# CV_Recorder.net
KiCad netlist of a schematic drawn in EAGLE
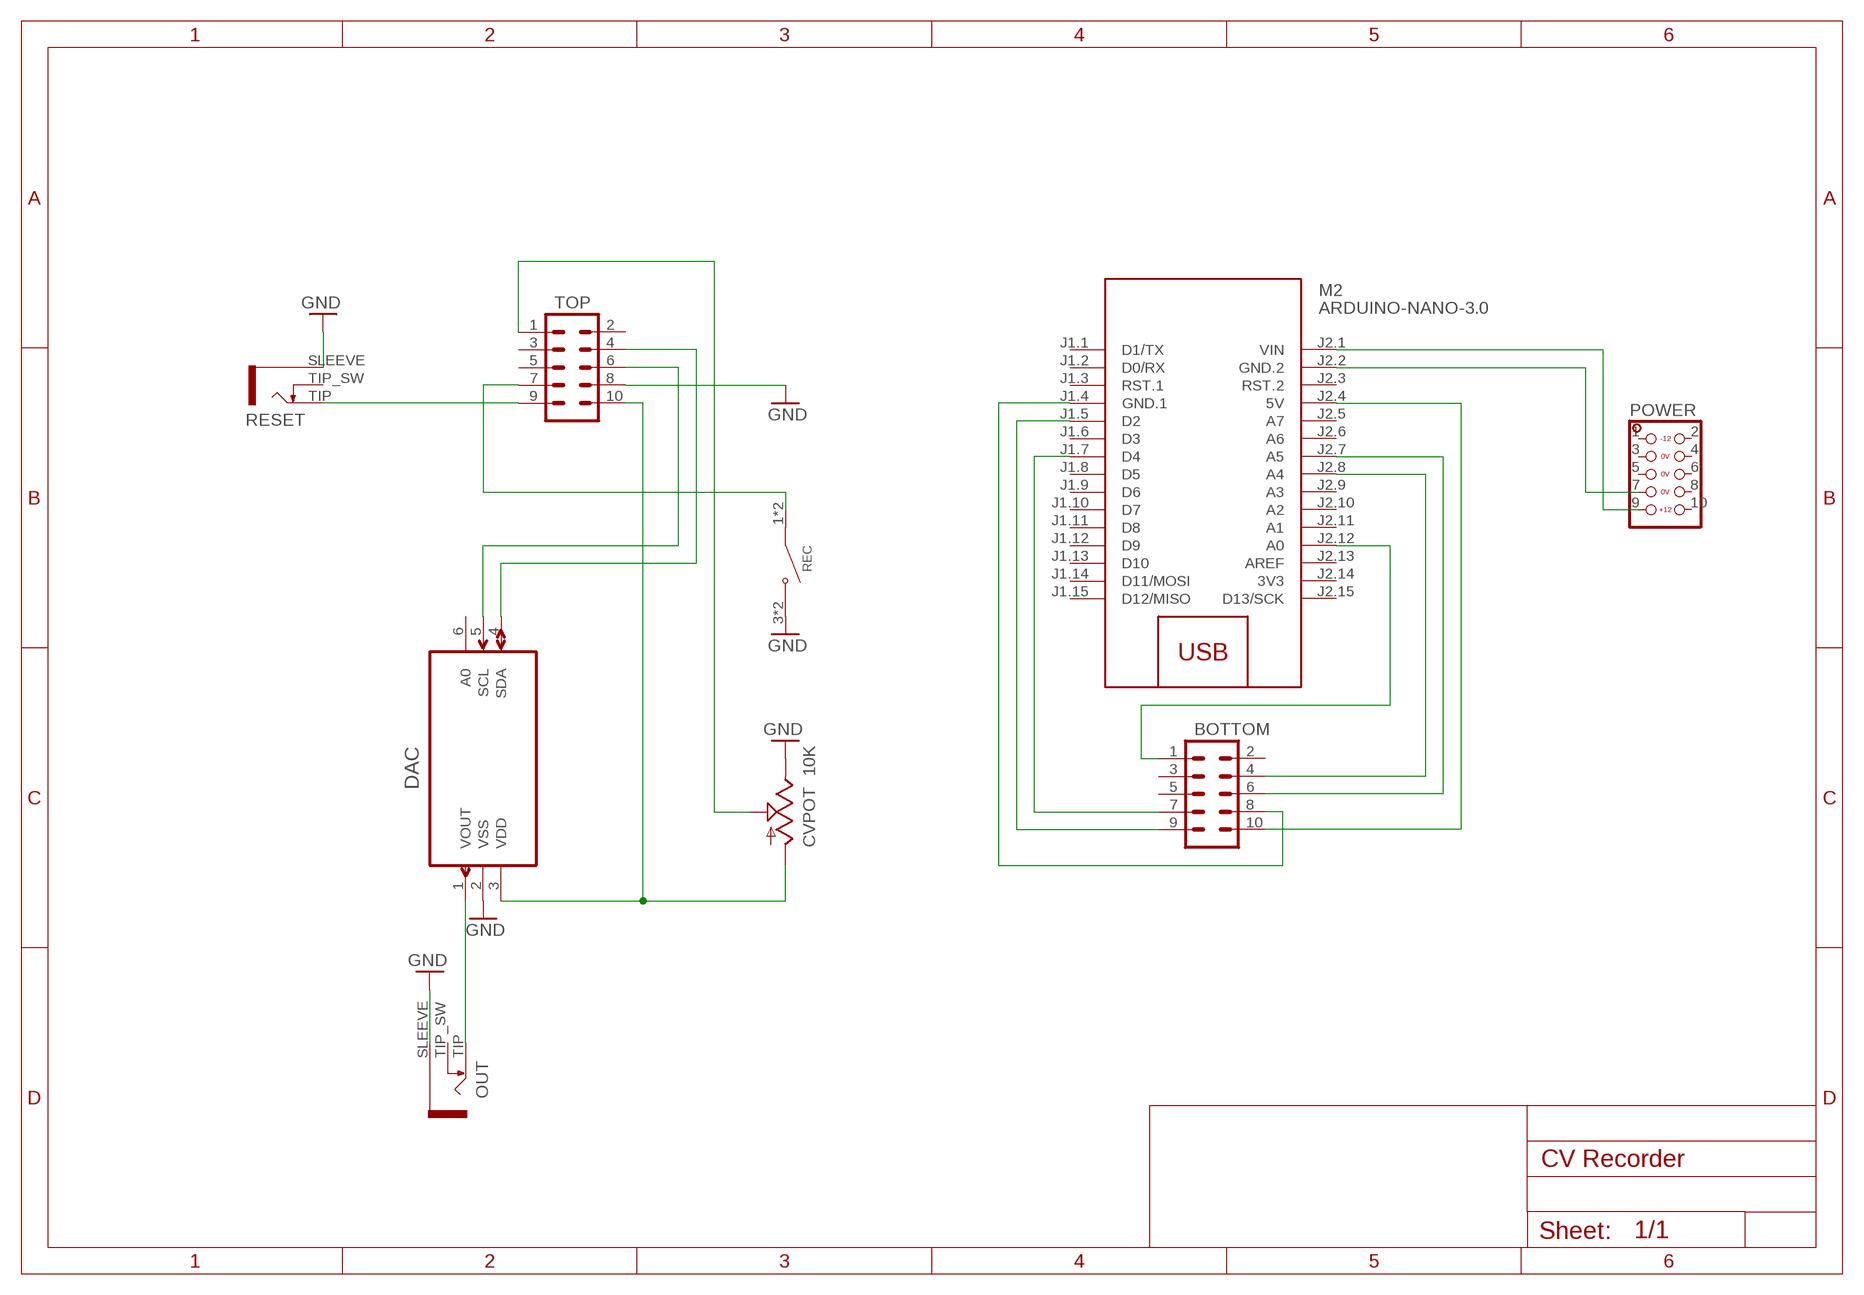
[diagram p0: schematic, sheet 1]

(export (version "E")
  (design (tool "Eeschema 10.0.6"))
  (components
    (comp (ref "BOTTOM")
      (value "M05X2PTH")
      (footprint "eagle-import:2X5")
      (libsource (lib "eagle-import") (part "M05X2PTH"))
    )
    (comp (ref "CVPOT")
      (value "10K")
      (footprint "eagle-import:ALPS_POT")
      (libsource (lib "eagle-import") (part "POT"))
    )
    (comp (ref "DAC")
      (value "MCP4725A0T-E/CH")
      (footprint "eagle-import:SOT95P270X145-6N")
      (libsource (lib "eagle-import") (part "MCP4725A0T-E/CH"))
    )
    (comp (ref "M2")
      (value "ARDUINO-NANO-3.0")
      (footprint "eagle-import:ARDUINO-NANO-3.0")
      (libsource (lib "eagle-import") (part "ARDUINO-NANO-3.0"))
    )
    (comp (ref "OUT")
      (value "JACK-3_5MM-MONO-SW-ALT")
      (footprint "eagle-import:WQP_PJ301M_ALT")
      (libsource (lib "eagle-import") (part "JACK-3_5MM-MONO-SW-ALT"))
    )
    (comp (ref "POWER")
      (value "EUROPWR_2X05-OPEN")
      (footprint "eagle-import:2X05_EUROPWR_OPEN")
      (libsource (lib "eagle-import") (part "EUROPWR_2X05-OPEN"))
    )
    (comp (ref "REC")
      (value "D6R90_F1_LFS")
      (footprint "eagle-import:SW_D6R90_F1_LFS")
      (fields (field (name "MF") "C&K") (field (name "MP") "D6R90 F1 LFS"))
      (libsource (lib "eagle-import") (part "D6R90_F1_LFS"))
    )
    (comp (ref "RESET")
      (value "JACK-3_5MM-MONO-SW-ALT")
      (footprint "eagle-import:WQP_PJ301M_ALT")
      (libsource (lib "eagle-import") (part "JACK-3_5MM-MONO-SW-ALT"))
    )
    (comp (ref "TOP")
      (value "M05X2PTH")
      (footprint "eagle-import:2X5")
      (libsource (lib "eagle-import") (part "M05X2PTH"))
    )
  )
  (nets
    (net (code "1") (name "/3V3") (class "Default")
      (node (ref "M2") (pin "J2.14") (pinfunction "3V3_J2.14") (pintype "power_in"))
    )
    (net (code "2") (name "GND") (class "Default")
      (node (ref "CVPOT") (pin "P$1") (pinfunction "3_P$1") (pintype "passive"))
      (node (ref "DAC") (pin "2") (pinfunction "VSS_2") (pintype "power_in"))
      (node (ref "OUT") (pin "SLEEVE") (pinfunction "SLEEVE_SLEEVE") (pintype "passive"))
      (node (ref "REC") (pin "3") (pinfunction "NO_3") (pintype "passive"))
      (node (ref "REC") (pin "4") (pinfunction "NO_4") (pintype "passive"))
      (node (ref "RESET") (pin "SLEEVE") (pinfunction "SLEEVE_SLEEVE") (pintype "passive"))
      (node (ref "TOP") (pin "8") (pinfunction "8_8") (pintype "passive"))
    )
    (net (code "3") (name "Net-(CVPOT-1)") (class "Default")
      (node (ref "CVPOT") (pin "P$3") (pinfunction "1_P$3") (pintype "passive"))
      (node (ref "DAC") (pin "3") (pinfunction "VDD_3") (pintype "power_in"))
      (node (ref "TOP") (pin "10") (pinfunction "10_10") (pintype "passive"))
    )
    (net (code "4") (name "Net-(CVPOT-2)") (class "Default")
      (node (ref "CVPOT") (pin "P$2") (pinfunction "2_P$2") (pintype "passive"))
      (node (ref "TOP") (pin "1") (pinfunction "1_1") (pintype "passive"))
    )
    (net (code "5") (name "Net-(DAC-SCL)") (class "Default")
      (node (ref "DAC") (pin "5") (pinfunction "SCL_5") (pintype "input"))
      (node (ref "TOP") (pin "6") (pinfunction "6_6") (pintype "passive"))
    )
    (net (code "6") (name "Net-(DAC-SDA)") (class "Default")
      (node (ref "DAC") (pin "4") (pinfunction "SDA_4") (pintype "bidirectional"))
      (node (ref "TOP") (pin "4") (pinfunction "4_4") (pintype "passive"))
    )
    (net (code "7") (name "Net-(DAC-VOUT)") (class "Default")
      (node (ref "DAC") (pin "1") (pinfunction "VOUT_1") (pintype "output"))
      (node (ref "OUT") (pin "TIP") (pinfunction "TIP_TIP") (pintype "passive"))
    )
    (net (code "8") (name "Net-(M2-5V)") (class "Default")
      (node (ref "BOTTOM") (pin "10") (pinfunction "10_10") (pintype "passive"))
      (node (ref "M2") (pin "J2.4") (pinfunction "5V_J2.4") (pintype "power_in"))
    )
    (net (code "9") (name "Net-(M2-A0)") (class "Default")
      (node (ref "BOTTOM") (pin "1") (pinfunction "1_1") (pintype "passive"))
      (node (ref "M2") (pin "J2.12") (pinfunction "A0_J2.12") (pintype "bidirectional"))
    )
    (net (code "10") (name "Net-(M2-A4)") (class "Default")
      (node (ref "BOTTOM") (pin "4") (pinfunction "4_4") (pintype "passive"))
      (node (ref "M2") (pin "J2.8") (pinfunction "A4_J2.8") (pintype "bidirectional"))
    )
    (net (code "11") (name "Net-(M2-A5)") (class "Default")
      (node (ref "BOTTOM") (pin "6") (pinfunction "6_6") (pintype "passive"))
      (node (ref "M2") (pin "J2.7") (pinfunction "A5_J2.7") (pintype "bidirectional"))
    )
    (net (code "12") (name "Net-(M2-D2)") (class "Default")
      (node (ref "BOTTOM") (pin "9") (pinfunction "9_9") (pintype "passive"))
      (node (ref "M2") (pin "J1.5") (pinfunction "D2_J1.5") (pintype "bidirectional"))
    )
    (net (code "13") (name "Net-(M2-D4)") (class "Default")
      (node (ref "BOTTOM") (pin "7") (pinfunction "7_7") (pintype "passive"))
      (node (ref "M2") (pin "J1.7") (pinfunction "D4_J1.7") (pintype "bidirectional"))
    )
    (net (code "14") (name "Net-(M2-GND.1)") (class "Default")
      (node (ref "BOTTOM") (pin "8") (pinfunction "8_8") (pintype "passive"))
      (node (ref "M2") (pin "J1.4") (pinfunction "GND.1_J1.4") (pintype "power_in"))
    )
    (net (code "15") (name "Net-(M2-GND.2)") (class "Default")
      (node (ref "M2") (pin "J2.2") (pinfunction "GND.2_J2.2") (pintype "power_in"))
      (node (ref "POWER") (pin "7") (pinfunction "7_7") (pintype "passive"))
    )
    (net (code "16") (name "Net-(M2-VIN)") (class "Default")
      (node (ref "M2") (pin "J2.1") (pinfunction "VIN_J2.1") (pintype "power_in"))
      (node (ref "POWER") (pin "9") (pinfunction "9_9") (pintype "passive"))
    )
    (net (code "17") (name "Net-(REC-COM-Pad1)") (class "Default")
      (node (ref "REC") (pin "1") (pinfunction "COM_1") (pintype "passive"))
      (node (ref "REC") (pin "2") (pinfunction "COM_2") (pintype "passive"))
      (node (ref "TOP") (pin "7") (pinfunction "7_7") (pintype "passive"))
    )
    (net (code "18") (name "Net-(RESET-PadTIP)") (class "Default")
      (node (ref "RESET") (pin "TIP") (pinfunction "TIP_TIP") (pintype "passive"))
      (node (ref "TOP") (pin "9") (pinfunction "9_9") (pintype "passive"))
    )
    (net (code "19") (name "unconnected-(BOTTOM-Pad2)") (class "Default")
      (node (ref "BOTTOM") (pin "2") (pinfunction "2_2") (pintype "passive"))
    )
    (net (code "20") (name "unconnected-(BOTTOM-Pad3)") (class "Default")
      (node (ref "BOTTOM") (pin "3") (pinfunction "3_3") (pintype "passive"))
    )
    (net (code "21") (name "unconnected-(BOTTOM-Pad5)") (class "Default")
      (node (ref "BOTTOM") (pin "5") (pinfunction "5_5") (pintype "passive"))
    )
    (net (code "22") (name "unconnected-(DAC-A0-Pad6)") (class "Default")
      (node (ref "DAC") (pin "6") (pinfunction "A0_6") (pintype "passive"))
    )
    (net (code "23") (name "unconnected-(M2-A1-PadJ2.11)") (class "Default")
      (node (ref "M2") (pin "J2.11") (pinfunction "A1_J2.11") (pintype "bidirectional"))
    )
    (net (code "24") (name "unconnected-(M2-A2-PadJ2.10)") (class "Default")
      (node (ref "M2") (pin "J2.10") (pinfunction "A2_J2.10") (pintype "bidirectional"))
    )
    (net (code "25") (name "unconnected-(M2-A3-PadJ2.9)") (class "Default")
      (node (ref "M2") (pin "J2.9") (pinfunction "A3_J2.9") (pintype "bidirectional"))
    )
    (net (code "26") (name "unconnected-(M2-A6-PadJ2.6)") (class "Default")
      (node (ref "M2") (pin "J2.6") (pinfunction "A6_J2.6") (pintype "bidirectional"))
    )
    (net (code "27") (name "unconnected-(M2-A7-PadJ2.5)") (class "Default")
      (node (ref "M2") (pin "J2.5") (pinfunction "A7_J2.5") (pintype "bidirectional"))
    )
    (net (code "28") (name "unconnected-(M2-AREF-PadJ2.13)") (class "Default")
      (node (ref "M2") (pin "J2.13") (pinfunction "AREF_J2.13") (pintype "bidirectional"))
    )
    (net (code "29") (name "unconnected-(M2-D0{slash}RX-PadJ1.2)") (class "Default")
      (node (ref "M2") (pin "J1.2") (pinfunction "D0/RX_J1.2") (pintype "bidirectional"))
    )
    (net (code "30") (name "unconnected-(M2-D1{slash}TX-PadJ1.1)") (class "Default")
      (node (ref "M2") (pin "J1.1") (pinfunction "D1/TX_J1.1") (pintype "bidirectional"))
    )
    (net (code "31") (name "unconnected-(M2-D3-PadJ1.6)") (class "Default")
      (node (ref "M2") (pin "J1.6") (pinfunction "D3_J1.6") (pintype "bidirectional"))
    )
    (net (code "32") (name "unconnected-(M2-D5-PadJ1.8)") (class "Default")
      (node (ref "M2") (pin "J1.8") (pinfunction "D5_J1.8") (pintype "bidirectional"))
    )
    (net (code "33") (name "unconnected-(M2-D6-PadJ1.9)") (class "Default")
      (node (ref "M2") (pin "J1.9") (pinfunction "D6_J1.9") (pintype "bidirectional"))
    )
    (net (code "34") (name "unconnected-(M2-D7-PadJ1.10)") (class "Default")
      (node (ref "M2") (pin "J1.10") (pinfunction "D7_J1.10") (pintype "bidirectional"))
    )
    (net (code "35") (name "unconnected-(M2-D8-PadJ1.11)") (class "Default")
      (node (ref "M2") (pin "J1.11") (pinfunction "D8_J1.11") (pintype "bidirectional"))
    )
    (net (code "36") (name "unconnected-(M2-D9-PadJ1.12)") (class "Default")
      (node (ref "M2") (pin "J1.12") (pinfunction "D9_J1.12") (pintype "bidirectional"))
    )
    (net (code "37") (name "unconnected-(M2-D10-PadJ1.13)") (class "Default")
      (node (ref "M2") (pin "J1.13") (pinfunction "D10_J1.13") (pintype "bidirectional"))
    )
    (net (code "38") (name "unconnected-(M2-D11{slash}MOSI-PadJ1.14)") (class "Default")
      (node (ref "M2") (pin "J1.14") (pinfunction "D11/MOSI_J1.14") (pintype "bidirectional"))
    )
    (net (code "39") (name "unconnected-(M2-D12{slash}MISO-PadJ1.15)") (class "Default")
      (node (ref "M2") (pin "J1.15") (pinfunction "D12/MISO_J1.15") (pintype "bidirectional"))
    )
    (net (code "40") (name "unconnected-(M2-D13{slash}SCK-PadJ2.15)") (class "Default")
      (node (ref "M2") (pin "J2.15") (pinfunction "D13/SCK_J2.15") (pintype "bidirectional"))
    )
    (net (code "41") (name "unconnected-(M2-RST.1-PadJ1.3)") (class "Default")
      (node (ref "M2") (pin "J1.3") (pinfunction "RST.1_J1.3") (pintype "bidirectional"))
    )
    (net (code "42") (name "unconnected-(M2-RST.2-PadJ2.3)") (class "Default")
      (node (ref "M2") (pin "J2.3") (pinfunction "RST.2_J2.3") (pintype "bidirectional"))
    )
    (net (code "43") (name "unconnected-(OUT-PadTIP_SW)") (class "Default")
      (node (ref "OUT") (pin "TIP_SW") (pinfunction "TIP_SW_TIP_SW") (pintype "passive"))
    )
    (net (code "44") (name "unconnected-(POWER-Pad1)") (class "Default")
      (node (ref "POWER") (pin "1") (pinfunction "1_1") (pintype "passive"))
    )
    (net (code "45") (name "unconnected-(POWER-Pad2)") (class "Default")
      (node (ref "POWER") (pin "2") (pinfunction "2_2") (pintype "passive"))
    )
    (net (code "46") (name "unconnected-(POWER-Pad3)") (class "Default")
      (node (ref "POWER") (pin "3") (pinfunction "3_3") (pintype "passive"))
    )
    (net (code "47") (name "unconnected-(POWER-Pad4)") (class "Default")
      (node (ref "POWER") (pin "4") (pinfunction "4_4") (pintype "passive"))
    )
    (net (code "48") (name "unconnected-(POWER-Pad5)") (class "Default")
      (node (ref "POWER") (pin "5") (pinfunction "5_5") (pintype "passive"))
    )
    (net (code "49") (name "unconnected-(POWER-Pad6)") (class "Default")
      (node (ref "POWER") (pin "6") (pinfunction "6_6") (pintype "passive"))
    )
    (net (code "50") (name "unconnected-(POWER-Pad8)") (class "Default")
      (node (ref "POWER") (pin "8") (pinfunction "8_8") (pintype "passive"))
    )
    (net (code "51") (name "unconnected-(POWER-Pad10)") (class "Default")
      (node (ref "POWER") (pin "10") (pinfunction "10_10") (pintype "passive"))
    )
    (net (code "52") (name "unconnected-(RESET-PadTIP_SW)") (class "Default")
      (node (ref "RESET") (pin "TIP_SW") (pinfunction "TIP_SW_TIP_SW") (pintype "passive"))
    )
    (net (code "53") (name "unconnected-(TOP-Pad2)") (class "Default")
      (node (ref "TOP") (pin "2") (pinfunction "2_2") (pintype "passive"))
    )
    (net (code "54") (name "unconnected-(TOP-Pad3)") (class "Default")
      (node (ref "TOP") (pin "3") (pinfunction "3_3") (pintype "passive"))
    )
    (net (code "55") (name "unconnected-(TOP-Pad5)") (class "Default")
      (node (ref "TOP") (pin "5") (pinfunction "5_5") (pintype "passive"))
    )
  )
)
